# ShieldBoard_Schematic.net
KiCad netlist of a schematic drawn in Altium Designer
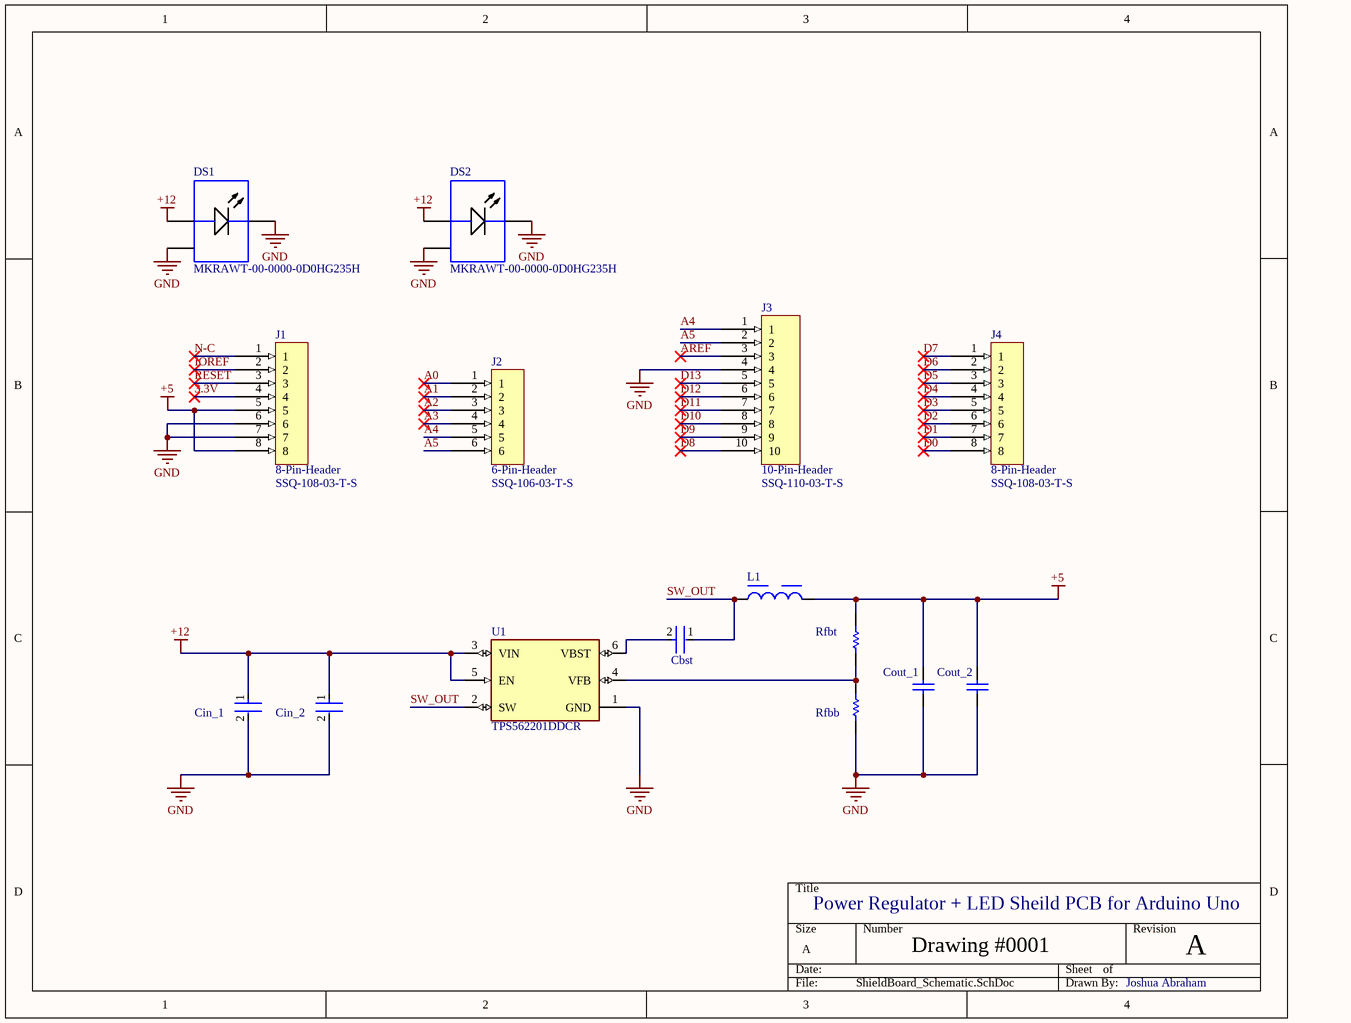
[diagram p0: ShieldBoard_Schematic.SchDoc]

(export (version "E")
  (design (tool "Eeschema 10.0.6"))
  (components
    (comp (ref "Cbst")
      (value "CC0805KRX7R8BB104")
      (footprint "FP-CC0805-0_85-MFG")
      (description "CAP CER 0.1UF 25V X7R 0805")
      (fields (field (name "TOLERANCE") "0.1") (field (name "MANUFACTURER") "Yageo"))
      (libsource (lib "Altium Content Vault") (part "11868f565c42a9108669ba33697ecf6"))
    )
    (comp (ref "Cin_1")
      (value "GRM21BR6YA106KE43L")
      (footprint "FP-GRM21B-0_2-e0_2_0_7-MFG")
      (description "Chip Multilayer Ceramic Capacitors for General Purpose, 0805, 10uF, X5R, 15%, 10%, 35V")
      (fields (field (name "TOLERANCE") "10%"))
      (libsource (lib "Altium Content Vault") (part "b4654b650e69147ec39a6b967a45e02"))
    )
    (comp (ref "Cin_2")
      (value "GRM21BR6YA106KE43L")
      (footprint "FP-GRM21B-0_2-e0_2_0_7-MFG")
      (description "Chip Multilayer Ceramic Capacitors for General Purpose, 0805, 10uF, X5R, 15%, 10%, 35V")
      (fields (field (name "TOLERANCE") "10%"))
      (libsource (lib "Altium Content Vault") (part "b4654b650e69147ec39a6b967a45e02"))
    )
    (comp (ref "Cout_1")
      (value "C1608X5R1A226M080AC")
      (footprint "CAPC1608X100X20ML10")
      (description "Chip Capacitor, 22 uF, +/- 20%, 10 V, -55 to 85 degC, 0603 (1608 Metric), RoHS, Tape and Reel")
      (fields (field (name "MANUFACTURER") "TDK") (field (name "TOLERANCE") "±20%"))
      (libsource (lib "Altium Content Vault") (part "CAP-NP-2"))
    )
    (comp (ref "Cout_2")
      (value "C1608X5R1A226M080AC")
      (footprint "CAPC1608X100X20ML10")
      (description "Chip Capacitor, 22 uF, +/- 20%, 10 V, -55 to 85 degC, 0603 (1608 Metric), RoHS, Tape and Reel")
      (fields (field (name "MANUFACTURER") "TDK") (field (name "TOLERANCE") "±20%"))
      (libsource (lib "Altium Content Vault") (part "CAP-NP-2"))
    )
    (comp (ref "DS1")
      (value "MKRAWT-00-0000-0D0HG235H")
      (footprint "CREE-MK-R-2_V")
      (description "LED, White, 12 V, 2-Pin SMD, RoHS, Tape and Reel")
      (libsource (lib "Cree_LED") (part "CMP-2100-00977-1"))
    )
    (comp (ref "DS2")
      (value "MKRAWT-00-0000-0D0HG235H")
      (footprint "CREE-MK-R-2_V")
      (description "LED, White, 12 V, 2-Pin SMD, RoHS, Tape and Reel")
      (libsource (lib "Cree_LED") (part "CMP-2100-00977-1"))
    )
    (comp (ref "J1")
      (value "8-Pin-Header")
      (footprint "8-Pin-Header-Footprint-1")
      (description "1x8 Header for arduino sheild board")
      (fields (field (name "MANUFACTURER PART NUMBER") "SSQ-108-03-T-S"))
      (libsource (lib "joshua_workspace") (part "8-Pin-Header"))
    )
    (comp (ref "J2")
      (value "6-Pin-Header")
      (footprint "6-Pin-Header-Footprint-1")
      (description "1x6 Header for arduino shield board")
      (fields (field (name "MANUFACTURER PART NUMBER") "SSQ-106-03-T-S"))
      (libsource (lib "joshua_workspace") (part "6-Pin-Header"))
    )
    (comp (ref "J3")
      (value "10-Pin-Header")
      (footprint "10-Pin-Header-Footprint-1")
      (description "1x10 Header for arduino sheild board")
      (fields (field (name "MANUFACTURER PART NUMBER") "SSQ-110-03-T-S"))
      (libsource (lib "joshua_workspace") (part "10-Pin-Header"))
    )
    (comp (ref "J4")
      (value "8-Pin-Header")
      (footprint "8-Pin-Header-Footprint-1")
      (description "1x8 Header for arduino sheild board")
      (fields (field (name "MANUFACTURER PART NUMBER") "SSQ-108-03-T-S"))
      (libsource (lib "joshua_workspace") (part "8-Pin-Header"))
    )
    (comp (ref "L1")
      (value "74437324033")
      (footprint "WE-LHMI_4020")
      (fields (field (name "TOLERANCE") "20%"))
      (libsource (lib "Altium Content Vault") (part "Inductor - 3"))
    )
    (comp (ref "Rfbb")
      (value "ERJ2RKF1002X")
      (footprint "RESC1005X40X25LL05T05")
      (description "Chip Resistor, 10 KOhm, +/- 1%, 0.1 W, -55 to 155 degC, 0402 (1005 Metric), RoHS, Tape and Reel")
      (fields (field (name "TOLERANCE") "1%") (field (name "MANUFACTURER") "Panasonic"))
      (libsource (lib "Altium Content Vault") (part "RES-2"))
    )
    (comp (ref "Rfbt")
      (value "CRCW020156K2FNED")
      (footprint "RESC0603X28X15NL05T05")
      (fields (field (name "MANUFACTURER") "Vishay Dale"))
      (libsource (lib "Altium Content Vault") (part "RES"))
    )
    (comp (ref "U1")
      (value "TPS562201DDCR")
      (footprint "FP-DDC0006A-IPC_C")
      (description "IC REG BUCK ADJ 2A TSOT23-6")
      (libsource (lib "Altium Content Vault") (part "957e164956730ea4bf6293280af19fc"))
    )
  )
  (nets
    (net (code "1") (name "+5") (class "Default")
      (node (ref "Cout_1") (pin "2") (pinfunction "2_2") (pintype "passive"))
      (node (ref "Cout_2") (pin "2") (pinfunction "2_2") (pintype "passive"))
      (node (ref "J1") (pin "5") (pinfunction "5_5") (pintype "input"))
      (node (ref "J1") (pin "8") (pinfunction "8_8") (pintype "input"))
      (node (ref "L1") (pin "2") (pinfunction "2_2") (pintype "passive"))
      (node (ref "Rfbt") (pin "2") (pinfunction "2_2") (pintype "passive"))
    )
    (net (code "2") (name "+12") (class "Default")
      (node (ref "Cin_1") (pin "1") (pinfunction "1_1") (pintype "passive"))
      (node (ref "Cin_2") (pin "1") (pinfunction "1_1") (pintype "passive"))
      (node (ref "DS1") (pin "1") (pinfunction "A_1") (pintype "passive"))
      (node (ref "DS2") (pin "1") (pinfunction "A_1") (pintype "passive"))
      (node (ref "U1") (pin "3") (pinfunction "VIN_3") (pintype "bidirectional"))
      (node (ref "U1") (pin "5") (pinfunction "EN_5") (pintype "input"))
    )
    (net (code "3") (name "/3.3V") (class "Default")
      (node (ref "J1") (pin "4") (pinfunction "4_4") (pintype "input+no_connect"))
    )
    (net (code "5") (name "/A0") (class "Default")
      (node (ref "J2") (pin "1") (pinfunction "1_1") (pintype "input+no_connect"))
    )
    (net (code "6") (name "/A1") (class "Default")
      (node (ref "J2") (pin "2") (pinfunction "2_2") (pintype "input+no_connect"))
    )
    (net (code "7") (name "/A2") (class "Default")
      (node (ref "J2") (pin "3") (pinfunction "3_3") (pintype "input+no_connect"))
    )
    (net (code "8") (name "/A3") (class "Default")
      (node (ref "J2") (pin "4") (pinfunction "4_4") (pintype "input+no_connect"))
    )
    (net (code "9") (name "/A4") (class "Default")
      (node (ref "J2") (pin "5") (pinfunction "5_5") (pintype "input"))
      (node (ref "J3") (pin "1") (pinfunction "1_1") (pintype "input"))
    )
    (net (code "10") (name "/A5") (class "Default")
      (node (ref "J2") (pin "6") (pinfunction "6_6") (pintype "input"))
      (node (ref "J3") (pin "2") (pinfunction "2_2") (pintype "input"))
    )
    (net (code "11") (name "/AREF") (class "Default")
      (node (ref "J3") (pin "3") (pinfunction "3_3") (pintype "input+no_connect"))
    )
    (net (code "12") (name "/D0") (class "Default")
      (node (ref "J4") (pin "8") (pinfunction "8_8") (pintype "input+no_connect"))
    )
    (net (code "13") (name "/D1") (class "Default")
      (node (ref "J4") (pin "7") (pinfunction "7_7") (pintype "input+no_connect"))
    )
    (net (code "14") (name "/D2") (class "Default")
      (node (ref "J4") (pin "6") (pinfunction "6_6") (pintype "input+no_connect"))
    )
    (net (code "15") (name "/D3") (class "Default")
      (node (ref "J4") (pin "5") (pinfunction "5_5") (pintype "input+no_connect"))
    )
    (net (code "16") (name "/D4") (class "Default")
      (node (ref "J4") (pin "4") (pinfunction "4_4") (pintype "input+no_connect"))
    )
    (net (code "17") (name "/D5") (class "Default")
      (node (ref "J4") (pin "3") (pinfunction "3_3") (pintype "input+no_connect"))
    )
    (net (code "18") (name "/D6") (class "Default")
      (node (ref "J4") (pin "2") (pinfunction "2_2") (pintype "input+no_connect"))
    )
    (net (code "19") (name "/D7") (class "Default")
      (node (ref "J4") (pin "1") (pinfunction "1_1") (pintype "input+no_connect"))
    )
    (net (code "20") (name "/D8") (class "Default")
      (node (ref "J3") (pin "10") (pinfunction "10_10") (pintype "input+no_connect"))
    )
    (net (code "21") (name "/D9") (class "Default")
      (node (ref "J3") (pin "9") (pinfunction "9_9") (pintype "input+no_connect"))
    )
    (net (code "22") (name "/D10") (class "Default")
      (node (ref "J3") (pin "8") (pinfunction "8_8") (pintype "input+no_connect"))
    )
    (net (code "23") (name "/D11") (class "Default")
      (node (ref "J3") (pin "7") (pinfunction "7_7") (pintype "input+no_connect"))
    )
    (net (code "24") (name "/D12") (class "Default")
      (node (ref "J3") (pin "6") (pinfunction "6_6") (pintype "input+no_connect"))
    )
    (net (code "25") (name "/D13") (class "Default")
      (node (ref "J3") (pin "5") (pinfunction "5_5") (pintype "input+no_connect"))
    )
    (net (code "26") (name "/IOREF") (class "Default")
      (node (ref "J1") (pin "2") (pinfunction "2_2") (pintype "input+no_connect"))
    )
    (net (code "27") (name "/N-C") (class "Default")
      (node (ref "J1") (pin "1") (pinfunction "1_1") (pintype "input+no_connect"))
    )
    (net (code "28") (name "/RESET") (class "Default")
      (node (ref "J1") (pin "3") (pinfunction "3_3") (pintype "input+no_connect"))
    )
    (net (code "29") (name "/SW_OUT") (class "Default")
      (node (ref "Cbst") (pin "1") (pinfunction "1_1") (pintype "passive"))
      (node (ref "L1") (pin "1") (pinfunction "1_1") (pintype "passive"))
      (node (ref "U1") (pin "2") (pinfunction "SW_2") (pintype "bidirectional"))
    )
    (net (code "30") (name "GND") (class "Default")
      (node (ref "Cin_1") (pin "2") (pinfunction "2_2") (pintype "passive"))
      (node (ref "Cin_2") (pin "2") (pinfunction "2_2") (pintype "passive"))
      (node (ref "Cout_1") (pin "1") (pinfunction "1_1") (pintype "passive"))
      (node (ref "Cout_2") (pin "1") (pinfunction "1_1") (pintype "passive"))
      (node (ref "DS1") (pin "2") (pinfunction "K_2") (pintype "passive"))
      (node (ref "DS1") (pin "3") (pinfunction "EP_3") (pintype "passive"))
      (node (ref "DS2") (pin "2") (pinfunction "K_2") (pintype "passive"))
      (node (ref "DS2") (pin "3") (pinfunction "EP_3") (pintype "passive"))
      (node (ref "J1") (pin "6") (pinfunction "6_6") (pintype "input"))
      (node (ref "J1") (pin "7") (pinfunction "7_7") (pintype "input"))
      (node (ref "J3") (pin "4") (pinfunction "4_4") (pintype "input"))
      (node (ref "Rfbb") (pin "1") (pinfunction "1_1") (pintype "passive"))
      (node (ref "U1") (pin "1") (pinfunction "GND_1") (pintype "power_in"))
    )
    (net (code "31") (name "Net-(U1-VBST)") (class "Default")
      (node (ref "Cbst") (pin "2") (pinfunction "2_2") (pintype "passive"))
      (node (ref "U1") (pin "6") (pinfunction "VBST_6") (pintype "bidirectional"))
    )
    (net (code "32") (name "Net-(U1-VFB)") (class "Default")
      (node (ref "Rfbb") (pin "2") (pinfunction "2_2") (pintype "passive"))
      (node (ref "Rfbt") (pin "1") (pinfunction "1_1") (pintype "passive"))
      (node (ref "U1") (pin "4") (pinfunction "VFB_4") (pintype "bidirectional"))
    )
  )
)
